# SCH_Beginner_project_2021-07-14.net
KiCad netlist of a schematic drawn in EasyEDA
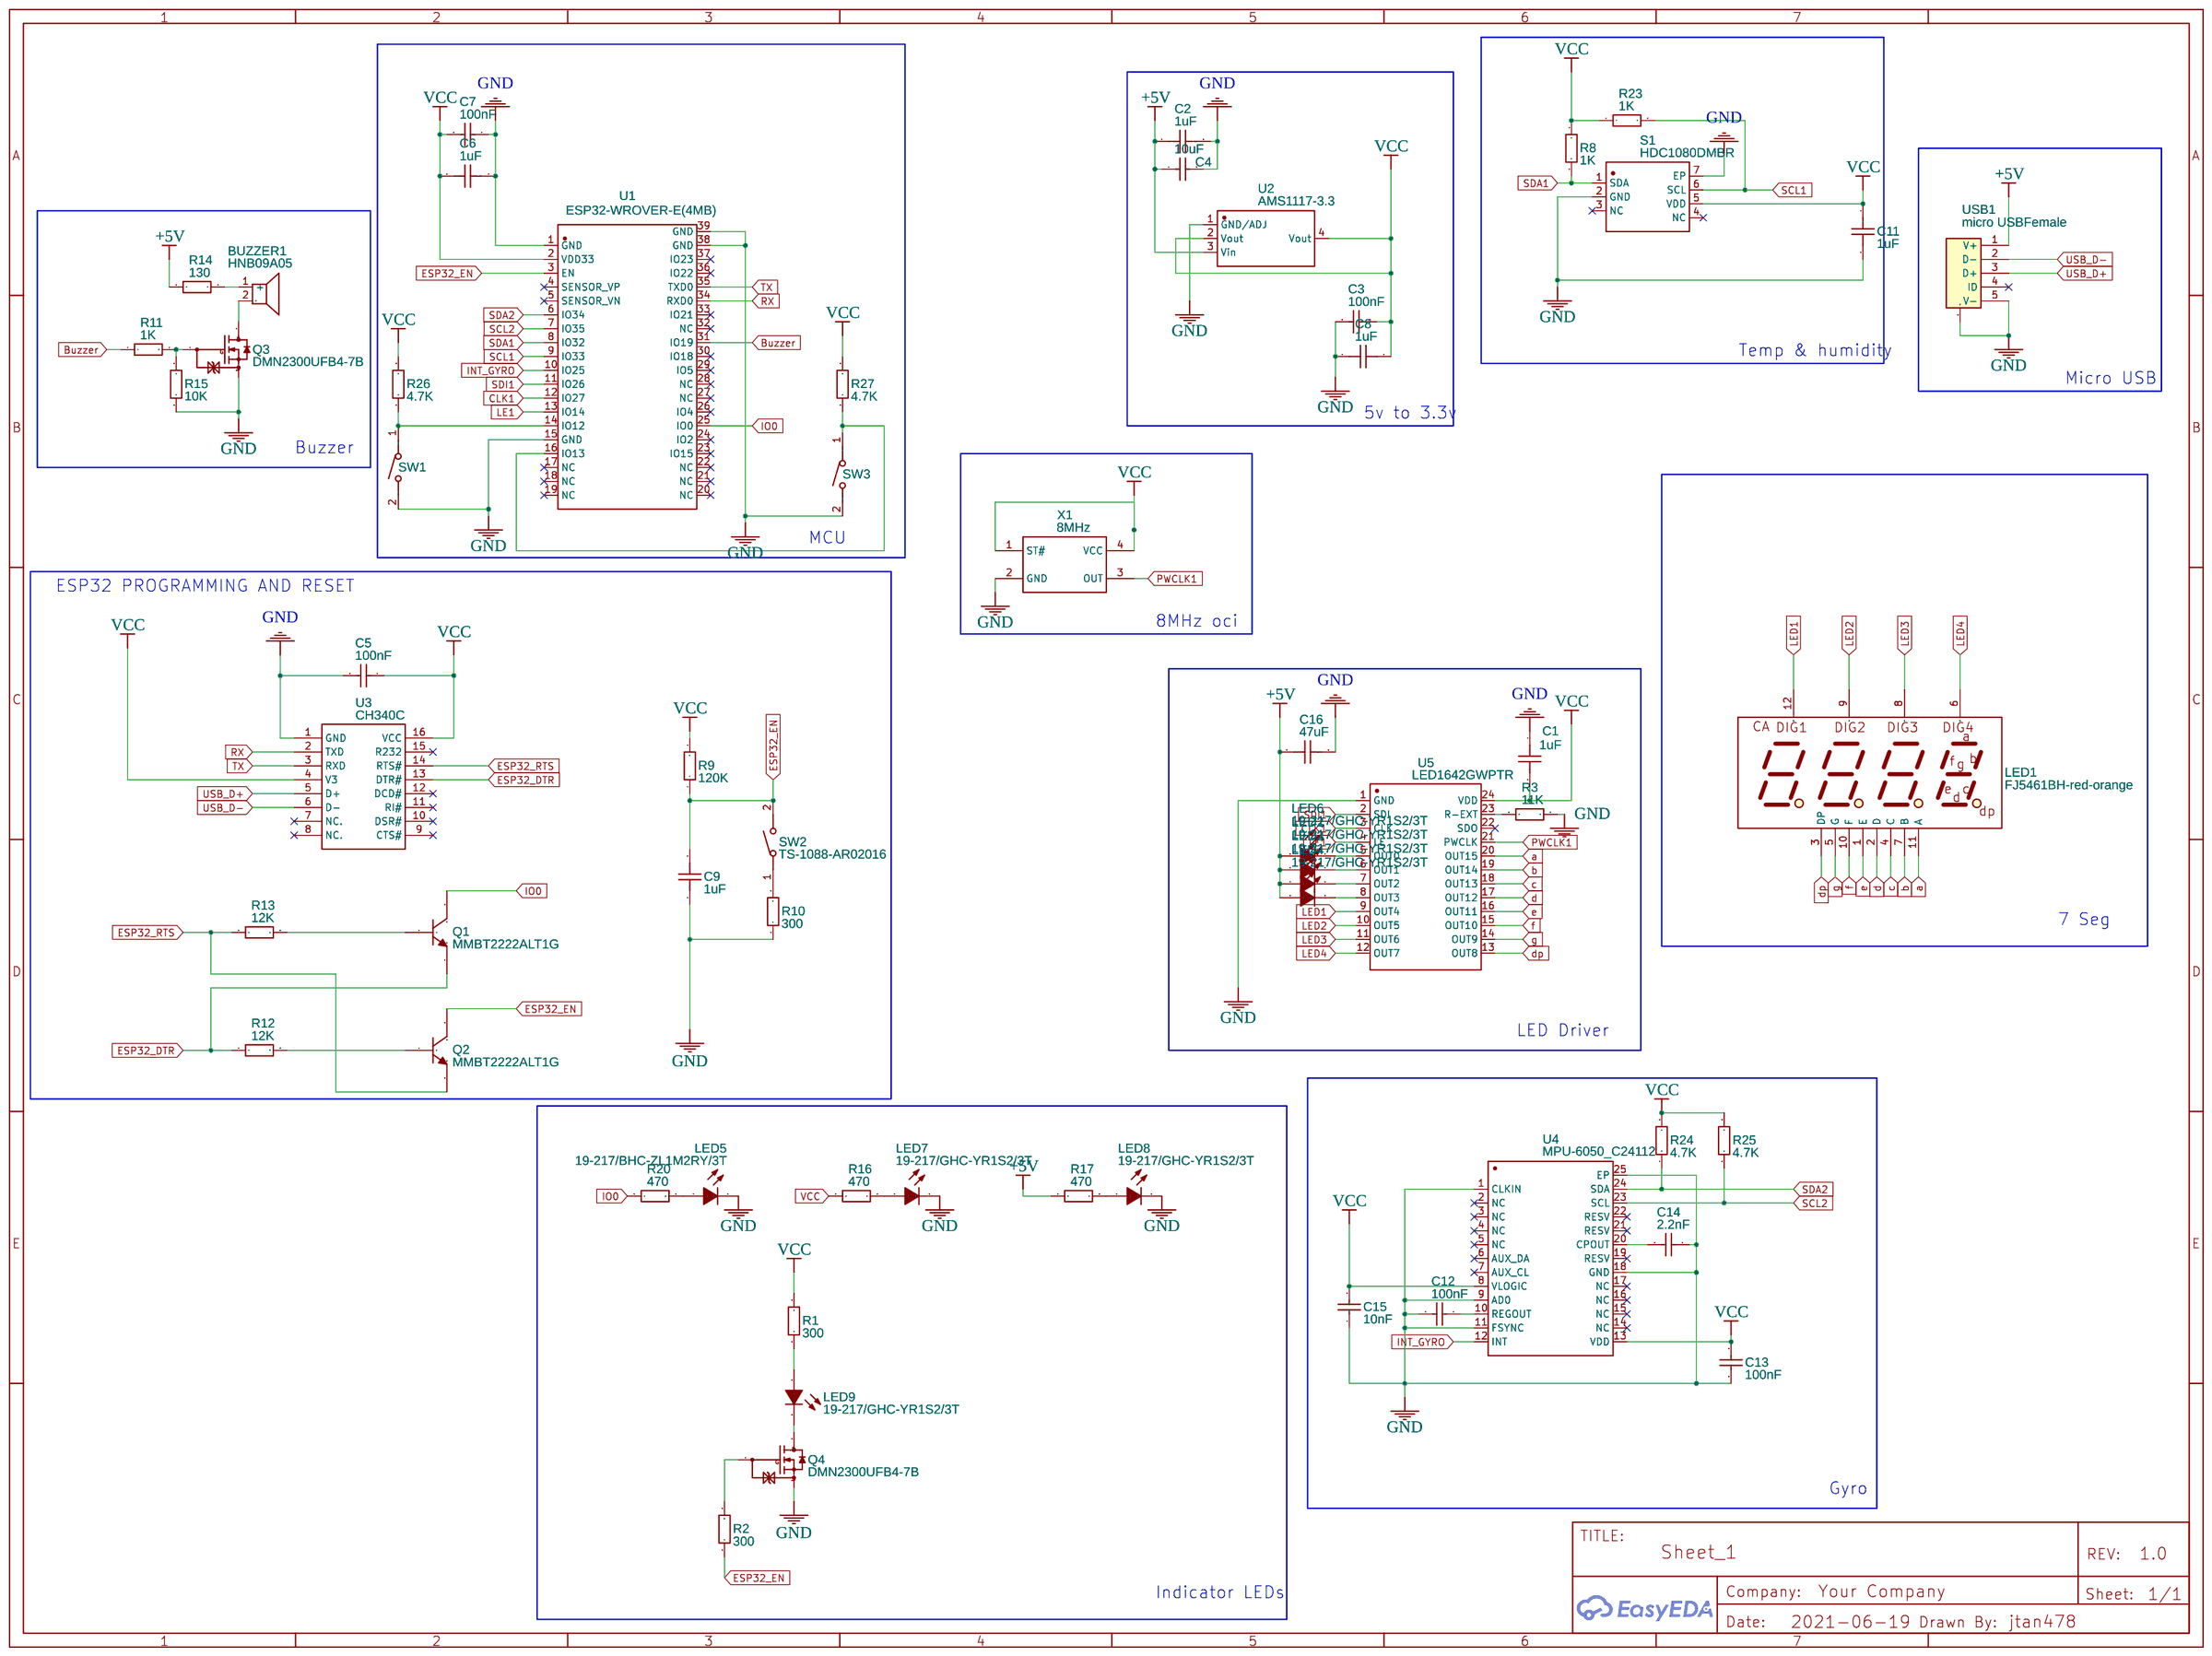
[diagram p0: schematic sheet]

(export (version "E")
  (design (tool "Eeschema 10.0.6"))
  (components
    (comp (ref "BUZZER1")
      (value "HNB09A05")
      (fields (field (name "BOM_Supplier Part") "C96493"))
      (libsource (lib "") (part "HNB09A05"))
    )
    (comp (ref "C1")
      (value "1uF")
      (fields
        (field (name "BOM_Manufacturer Part") "CL05A105KA5NQNC")
        (field (name "BOM_Supplier Part") "C52923")
      )
      (libsource (lib "") (part "CL05A105KA5NQNC_1"))
    )
    (comp (ref "C2")
      (value "1uF")
      (fields
        (field (name "BOM_Manufacturer Part") "CL05A105KA5NQNC")
        (field (name "BOM_Supplier Part") "C52923")
      )
      (libsource (lib "") (part "CL05A105KA5NQNC_3"))
    )
    (comp (ref "C3")
      (value "100nF")
      (fields
        (field (name "BOM_Manufacturer Part") "CL05B104KO5NNNC")
        (field (name "BOM_Supplier Part") "C1525")
      )
      (libsource (lib "") (part "CL05B104KO5NNNC"))
    )
    (comp (ref "C4")
      (value "10uF")
      (fields
        (field (name "BOM_Manufacturer Part") "CL05A106MQ5NUNC")
        (field (name "BOM_Supplier Part") "C15525")
      )
      (libsource (lib "") (part "CL05A106MQ5NUNC"))
    )
    (comp (ref "C5")
      (value "100nF")
      (fields
        (field (name "BOM_Manufacturer Part") "CL05B104KO5NNNC")
        (field (name "BOM_Supplier Part") "C1525")
      )
      (libsource (lib "") (part "CL05B104KO5NNNC"))
    )
    (comp (ref "C6")
      (value "1uF")
      (fields
        (field (name "BOM_Manufacturer Part") "CL05A105KA5NQNC")
        (field (name "BOM_Supplier Part") "C52923")
      )
      (libsource (lib "") (part "CL05A105KA5NQNC_2"))
    )
    (comp (ref "C7")
      (value "100nF")
      (fields
        (field (name "BOM_Manufacturer Part") "CL05B104KO5NNNC")
        (field (name "BOM_Supplier Part") "C1525")
      )
      (libsource (lib "") (part "CL05B104KO5NNNC"))
    )
    (comp (ref "C8")
      (value "1uF")
      (fields
        (field (name "BOM_Manufacturer Part") "CL05A105KA5NQNC")
        (field (name "BOM_Supplier Part") "C52923")
      )
      (libsource (lib "") (part "CL05A105KA5NQNC_3"))
    )
    (comp (ref "C9")
      (value "1uF")
      (fields
        (field (name "BOM_Manufacturer Part") "CL05A105KA5NQNC")
        (field (name "BOM_Supplier Part") "C52923")
      )
      (libsource (lib "") (part "CL05A105KA5NQNC"))
    )
    (comp (ref "C11")
      (value "1uF")
      (fields
        (field (name "BOM_Manufacturer Part") "CL05A105KA5NQNC")
        (field (name "BOM_Supplier Part") "C52923")
      )
      (libsource (lib "") (part "CL05A105KA5NQNC_1"))
    )
    (comp (ref "C12")
      (value "100nF")
      (fields
        (field (name "BOM_Manufacturer Part") "CL05B104KO5NNNC")
        (field (name "BOM_Supplier Part") "C1525")
      )
      (libsource (lib "") (part "CL05B104KO5NNNC"))
    )
    (comp (ref "C13")
      (value "100nF")
      (fields
        (field (name "BOM_Manufacturer Part") "CL05B104KO5NNNC")
        (field (name "BOM_Supplier Part") "C1525")
      )
      (libsource (lib "") (part "CL05B104KO5NNNC_1"))
    )
    (comp (ref "C14")
      (value "2.2nF")
      (fields
        (field (name "BOM_Manufacturer Part") "0402B222K500NT")
        (field (name "BOM_Supplier Part") "C1531")
      )
      (libsource (lib "") (part "0402B222K500NT"))
    )
    (comp (ref "C15")
      (value "10nF")
      (fields
        (field (name "BOM_Manufacturer Part") "CL05B103KB5NNNC")
        (field (name "BOM_Supplier Part") "C15195")
      )
      (libsource (lib "") (part "CL05B103KB5NNNC"))
    )
    (comp (ref "C16")
      (value "47uF")
      (fields
        (field (name "BOM_Manufacturer Part") "CL31A476MPHNNNE")
        (field (name "BOM_Supplier Part") "C96123")
      )
      (libsource (lib "") (part "CL31A476MPHNNNE"))
    )
    (comp (ref "LED1")
      (value "FJ5461BH-red-orange")
      (fields
        (field (name "BOM_Manufacturer Part") "FJ5461BH 橙红")
        (field (name "BOM_Supplier Part") "C10713")
      )
      (libsource (lib "") (part "FJ5461BH-red-orange"))
    )
    (comp (ref "LED2")
      (value "19-217/GHC-YR1S2/3T")
      (fields (field (name "BOM_Supplier Part") "C72043"))
      (libsource (lib "") (part "19-217/GHC-YR1S2/3T"))
    )
    (comp (ref "LED3")
      (value "19-217/GHC-YR1S2/3T")
      (fields (field (name "BOM_Supplier Part") "C72043"))
      (libsource (lib "") (part "19-217/GHC-YR1S2/3T"))
    )
    (comp (ref "LED4")
      (value "19-217/GHC-YR1S2/3T")
      (fields (field (name "BOM_Supplier Part") "C72043"))
      (libsource (lib "") (part "19-217/GHC-YR1S2/3T"))
    )
    (comp (ref "LED5")
      (value "19-217/BHC-ZL1M2RY/3T")
      (fields (field (name "BOM_Supplier Part") "C72041"))
      (libsource (lib "") (part "19-217/BHC-ZL1M2RY/3T"))
    )
    (comp (ref "LED6")
      (value "19-217/GHC-YR1S2/3T")
      (fields (field (name "BOM_Supplier Part") "C72043"))
      (libsource (lib "") (part "19-217/GHC-YR1S2/3T"))
    )
    (comp (ref "LED7")
      (value "19-217/GHC-YR1S2/3T")
      (fields (field (name "BOM_Supplier Part") "C72043"))
      (libsource (lib "") (part "19-217/GHC-YR1S2/3T"))
    )
    (comp (ref "LED8")
      (value "19-217/GHC-YR1S2/3T")
      (fields (field (name "BOM_Supplier Part") "C72043"))
      (libsource (lib "") (part "19-217/GHC-YR1S2/3T"))
    )
    (comp (ref "LED9")
      (value "19-217/GHC-YR1S2/3T")
      (fields (field (name "BOM_Supplier Part") "C72043"))
      (libsource (lib "") (part "19-217/GHC-YR1S2/3T_1"))
    )
    (comp (ref "Q1")
      (value "MMBT2222ALT1G")
      (fields (field (name "BOM_Supplier Part") "C82460"))
      (libsource (lib "") (part "MMBT2222ALT1G"))
    )
    (comp (ref "Q2")
      (value "MMBT2222ALT1G")
      (fields (field (name "BOM_Supplier Part") "C82460"))
      (libsource (lib "") (part "MMBT2222ALT1G"))
    )
    (comp (ref "Q3")
      (value "DMN2300UFB4-7B")
      (fields (field (name "BOM_Supplier Part") "C154728"))
      (libsource (lib "") (part "DMN2300UFB4-7B"))
    )
    (comp (ref "Q4")
      (value "DMN2300UFB4-7B")
      (fields (field (name "BOM_Supplier Part") "C154728"))
      (libsource (lib "") (part "DMN2300UFB4-7B"))
    )
    (comp (ref "R1")
      (value "300")
      (fields
        (field (name "BOM_Manufacturer Part") "0402WGF3000TCE")
        (field (name "BOM_Supplier Part") "C25102")
      )
      (libsource (lib "") (part "0402WGF3000TCE"))
    )
    (comp (ref "R2")
      (value "300")
      (fields
        (field (name "BOM_Manufacturer Part") "0402WGF3000TCE")
        (field (name "BOM_Supplier Part") "C25102")
      )
      (libsource (lib "") (part "0402WGF3000TCE"))
    )
    (comp (ref "R3")
      (value "11K")
      (fields
        (field (name "BOM_Manufacturer Part") "0603WAF1102T5E")
        (field (name "BOM_Supplier Part") "C25950")
      )
      (libsource (lib "") (part "0603WAF1102T5E"))
    )
    (comp (ref "R8")
      (value "1K")
      (fields
        (field (name "BOM_Manufacturer Part") "0603WAF1001T5E")
        (field (name "BOM_Supplier Part") "C21190")
      )
      (libsource (lib "") (part "0603WAF1001T5E_1"))
    )
    (comp (ref "R9")
      (value "120K")
      (fields
        (field (name "BOM_Manufacturer Part") "0402WGF1203TCE")
        (field (name "BOM_Supplier Part") "C25750")
      )
      (libsource (lib "") (part "0402WGF1203TCE"))
    )
    (comp (ref "R10")
      (value "300")
      (fields
        (field (name "BOM_Manufacturer Part") "0402WGF3000TCE")
        (field (name "BOM_Supplier Part") "C25102")
      )
      (libsource (lib "") (part "0402WGF3000TCE"))
    )
    (comp (ref "R11")
      (value "1K")
      (fields
        (field (name "BOM_Manufacturer Part") "0603WAF1001T5E")
        (field (name "BOM_Supplier Part") "C21190")
      )
      (libsource (lib "") (part "0603WAF1001T5E"))
    )
    (comp (ref "R12")
      (value "12K")
      (fields
        (field (name "BOM_Manufacturer Part") "0402WGF1202TCE")
        (field (name "BOM_Supplier Part") "C25752")
      )
      (libsource (lib "") (part "0402WGF1202TCE"))
    )
    (comp (ref "R13")
      (value "12K")
      (fields
        (field (name "BOM_Manufacturer Part") "0402WGF1202TCE")
        (field (name "BOM_Supplier Part") "C25752")
      )
      (libsource (lib "") (part "0402WGF1202TCE"))
    )
    (comp (ref "R14")
      (value "130")
      (fields
        (field (name "BOM_Manufacturer Part") "0603WAF1300T5E")
        (field (name "BOM_Supplier Part") "C22796")
      )
      (libsource (lib "") (part "0603WAF1300T5E"))
    )
    (comp (ref "R15")
      (value "10K")
      (fields
        (field (name "BOM_Manufacturer Part") "0603WAF1002T5E")
        (field (name "BOM_Supplier Part") "C25804")
      )
      (libsource (lib "") (part "0603WAF1002T5E"))
    )
    (comp (ref "R16")
      (value "470")
      (fields
        (field (name "BOM_Manufacturer Part") "0402WGF4700TCE")
        (field (name "BOM_Supplier Part") "C25117")
      )
      (libsource (lib "") (part "0402WGF4700TCE"))
    )
    (comp (ref "R17")
      (value "470")
      (fields
        (field (name "BOM_Manufacturer Part") "0402WGF4700TCE")
        (field (name "BOM_Supplier Part") "C25117")
      )
      (libsource (lib "") (part "0402WGF4700TCE"))
    )
    (comp (ref "R20")
      (value "470")
      (fields
        (field (name "BOM_Manufacturer Part") "0402WGF4700TCE")
        (field (name "BOM_Supplier Part") "C25117")
      )
      (libsource (lib "") (part "0402WGF4700TCE"))
    )
    (comp (ref "R23")
      (value "1K")
      (fields
        (field (name "BOM_Manufacturer Part") "0603WAF1001T5E")
        (field (name "BOM_Supplier Part") "C21190")
      )
      (libsource (lib "") (part "0603WAF1001T5E"))
    )
    (comp (ref "R24")
      (value "4.7K")
      (fields
        (field (name "BOM_Manufacturer Part") "0402WGF4701TCE")
        (field (name "BOM_Supplier Part") "C25900")
      )
      (libsource (lib "") (part "0402WGF4701TCE"))
    )
    (comp (ref "R25")
      (value "4.7K")
      (fields
        (field (name "BOM_Manufacturer Part") "0402WGF4701TCE")
        (field (name "BOM_Supplier Part") "C25900")
      )
      (libsource (lib "") (part "0402WGF4701TCE"))
    )
    (comp (ref "R26")
      (value "4.7K")
      (fields
        (field (name "BOM_Manufacturer Part") "0402WGF4701TCE")
        (field (name "BOM_Supplier Part") "C25900")
      )
      (libsource (lib "") (part "0402WGF4701TCE"))
    )
    (comp (ref "R27")
      (value "4.7K")
      (fields
        (field (name "BOM_Manufacturer Part") "0402WGF4701TCE")
        (field (name "BOM_Supplier Part") "C25900")
      )
      (libsource (lib "") (part "0402WGF4701TCE"))
    )
    (comp (ref "S1")
      (value "HDC1080DMBR")
      (fields (field (name "BOM_Supplier Part") "C82227"))
      (libsource (lib "") (part "HDC1080DMBR"))
    )
    (comp (ref "SW1")
      (value "TS-1088-AR02016")
      (fields (field (name "BOM_Supplier Part") "C720477"))
      (libsource (lib "") (part "TS-1088-AR02016"))
    )
    (comp (ref "SW2")
      (value "TS-1088-AR02016")
      (fields (field (name "BOM_Supplier Part") "C720477"))
      (libsource (lib "") (part "TS-1088-AR02016_1"))
    )
    (comp (ref "SW3")
      (value "TS-1088-AR02016")
      (fields (field (name "BOM_Supplier Part") "C720477"))
      (libsource (lib "") (part "TS-1088-AR02016"))
    )
    (comp (ref "U1")
      (value "ESP32-WROVER-E(4MB)")
      (fields (field (name "BOM_Supplier Part") "C529587"))
      (libsource (lib "") (part "ESP32-WROVER-E(4MB)"))
    )
    (comp (ref "U2")
      (value "AMS1117-3.3")
      (fields (field (name "BOM_Supplier Part") "C6186"))
      (libsource (lib "") (part "AMS1117-3.3"))
    )
    (comp (ref "U3")
      (value "CH340C")
      (fields (field (name "BOM_Supplier Part") "C84681"))
      (libsource (lib "") (part "CH340C"))
    )
    (comp (ref "U4")
      (value "MPU-6050_C24112")
      (fields (field (name "BOM_Manufacturer Part") "MPU-6050") (field (name "BOM_Supplier Part") "C24112"))
      (libsource (lib "") (part "MPU-6050_C24112"))
    )
    (comp (ref "U5")
      (value "LED1642GWPTR")
      (fields (field (name "BOM_Supplier Part") "C131193"))
      (libsource (lib "") (part "LED1642GWPTR"))
    )
    (comp (ref "USB1")
      (value "micro USBFemale")
      (fields (field (name "BOM_Supplier Part") "C10418"))
      (libsource (lib "") (part "micro USBFemale"))
    )
    (comp (ref "X1")
      (value "8MHz")
      (fields
        (field (name "BOM_Manufacturer Part") "Q33310F70055100")
        (field (name "BOM_Supplier Part") "C70556")
      )
      (libsource (lib "") (part "Q33310F70055100"))
    )
  )
  (nets
    (net (code "1") (name "+5V") (class "Default")
      (node (ref "C16") (pin "1") (pinfunction "1_1") (pintype "unspecified"))
      (node (ref "C2") (pin "1") (pinfunction "1_1") (pintype "unspecified"))
      (node (ref "C4") (pin "1") (pinfunction "1_1") (pintype "input"))
      (node (ref "LED2") (pin "1") (pinfunction "A_1") (pintype "input"))
      (node (ref "LED3") (pin "1") (pinfunction "A_1") (pintype "input"))
      (node (ref "LED4") (pin "1") (pinfunction "A_1") (pintype "input"))
      (node (ref "LED6") (pin "1") (pinfunction "A_1") (pintype "input"))
      (node (ref "R14") (pin "1") (pinfunction "1_1") (pintype "input"))
      (node (ref "R17") (pin "1") (pinfunction "1_1") (pintype "input"))
      (node (ref "U2") (pin "3") (pinfunction "Vin_3") (pintype "unspecified"))
      (node (ref "USB1") (pin "1") (pinfunction "V+_1") (pintype "unspecified"))
    )
    (net (code "2") (name "Buzzer") (class "Default")
      (node (ref "R11") (pin "1") (pinfunction "1_1") (pintype "input"))
      (node (ref "U1") (pin "31") (pinfunction "IO19_31") (pintype "unspecified"))
    )
    (net (code "3") (name "CLK1") (class "Default")
      (node (ref "U1") (pin "12") (pinfunction "IO27_12") (pintype "unspecified"))
      (node (ref "U5") (pin "3") (pinfunction "CLK_3") (pintype "unspecified"))
    )
    (net (code "4") (name "ESP32_DTR") (class "Default")
      (node (ref "Q1") (pin "2") (pinfunction "E_2") (pintype "unspecified"))
      (node (ref "R12") (pin "1") (pinfunction "1_1") (pintype "input"))
      (node (ref "U3") (pin "13") (pinfunction "DTR#_13") (pintype "unspecified"))
    )
    (net (code "5") (name "ESP32_EN") (class "Default")
      (node (ref "C9") (pin "2") (pinfunction "2_2") (pintype "unspecified"))
      (node (ref "Q2") (pin "3") (pinfunction "C_3") (pintype "unspecified"))
      (node (ref "R2") (pin "1") (pinfunction "1_1") (pintype "input"))
      (node (ref "R9") (pin "1") (pinfunction "1_1") (pintype "input"))
      (node (ref "SW2") (pin "2") (pinfunction "2_2") (pintype "unspecified"))
      (node (ref "U1") (pin "3") (pinfunction "EN_3") (pintype "unspecified"))
    )
    (net (code "6") (name "ESP32_RTS") (class "Default")
      (node (ref "Q2") (pin "2") (pinfunction "E_2") (pintype "unspecified"))
      (node (ref "R13") (pin "1") (pinfunction "1_1") (pintype "input"))
      (node (ref "U3") (pin "14") (pinfunction "RTS#_14") (pintype "unspecified"))
    )
    (net (code "7") (name "GND") (class "Default")
      (node (ref "C1") (pin "1") (pinfunction "1_1") (pintype "unspecified"))
      (node (ref "C11") (pin "2") (pinfunction "2_2") (pintype "unspecified"))
      (node (ref "C12") (pin "2") (pinfunction "2_2") (pintype "input"))
      (node (ref "C13") (pin "2") (pinfunction "2_2") (pintype "input"))
      (node (ref "C14") (pin "1") (pinfunction "1_1") (pintype "input"))
      (node (ref "C15") (pin "1") (pinfunction "1_1") (pintype "input"))
      (node (ref "C16") (pin "2") (pinfunction "2_2") (pintype "unspecified"))
      (node (ref "C2") (pin "2") (pinfunction "2_2") (pintype "unspecified"))
      (node (ref "C3") (pin "2") (pinfunction "2_2") (pintype "input"))
      (node (ref "C4") (pin "2") (pinfunction "2_2") (pintype "input"))
      (node (ref "C5") (pin "2") (pinfunction "2_2") (pintype "input"))
      (node (ref "C6") (pin "1") (pinfunction "1_1") (pintype "unspecified"))
      (node (ref "C7") (pin "1") (pinfunction "1_1") (pintype "input"))
      (node (ref "C8") (pin "1") (pinfunction "1_1") (pintype "unspecified"))
      (node (ref "C9") (pin "1") (pinfunction "1_1") (pintype "unspecified"))
      (node (ref "LED5") (pin "2") (pinfunction "C_2") (pintype "input"))
      (node (ref "LED7") (pin "2") (pinfunction "C_2") (pintype "input"))
      (node (ref "LED8") (pin "2") (pinfunction "C_2") (pintype "input"))
      (node (ref "Q3") (pin "3") (pinfunction "S_3") (pintype "unspecified"))
      (node (ref "Q4") (pin "3") (pinfunction "S_3") (pintype "unspecified"))
      (node (ref "R10") (pin "1") (pinfunction "1_1") (pintype "input"))
      (node (ref "R15") (pin "2") (pinfunction "2_2") (pintype "input"))
      (node (ref "R3") (pin "2") (pinfunction "2_2") (pintype "input"))
      (node (ref "S1") (pin "2") (pinfunction "GND_2") (pintype "unspecified"))
      (node (ref "S1") (pin "7") (pinfunction "EP_7") (pintype "unspecified"))
      (node (ref "SW1") (pin "2") (pinfunction "2_2") (pintype "unspecified"))
      (node (ref "SW3") (pin "2") (pinfunction "2_2") (pintype "unspecified"))
      (node (ref "U1") (pin "1") (pinfunction "GND_1") (pintype "unspecified"))
      (node (ref "U1") (pin "15") (pinfunction "GND_15") (pintype "unspecified"))
      (node (ref "U1") (pin "38") (pinfunction "GND_38") (pintype "unspecified"))
      (node (ref "U1") (pin "39") (pinfunction "GND_39") (pintype "unspecified"))
      (node (ref "U2") (pin "1") (pinfunction "GND/ADJ_1") (pintype "unspecified"))
      (node (ref "U3") (pin "1") (pinfunction "GND_1") (pintype "unspecified"))
      (node (ref "U4") (pin "1") (pinfunction "CLKIN_1") (pintype "unspecified"))
      (node (ref "U4") (pin "11") (pinfunction "FSYNC_11") (pintype "unspecified"))
      (node (ref "U4") (pin "18") (pinfunction "GND_18") (pintype "unspecified"))
      (node (ref "U4") (pin "25") (pinfunction "EP_25") (pintype "unspecified"))
      (node (ref "U4") (pin "9") (pinfunction "AD0_9") (pintype "unspecified"))
      (node (ref "U5") (pin "1") (pinfunction "GND_1") (pintype "unspecified"))
      (node (ref "USB1") (pin "0") (pinfunction "MTN_0") (pintype "input"))
      (node (ref "USB1") (pin "5") (pinfunction "V-_5") (pintype "unspecified"))
      (node (ref "X1") (pin "2") (pinfunction "GND_2") (pintype "unspecified"))
    )
    (net (code "8") (name "INT_GYRO") (class "Default")
      (node (ref "U1") (pin "10") (pinfunction "IO25_10") (pintype "unspecified"))
      (node (ref "U4") (pin "12") (pinfunction "INT_12") (pintype "unspecified"))
    )
    (net (code "9") (name "IO0") (class "Default")
      (node (ref "Q1") (pin "3") (pinfunction "C_3") (pintype "unspecified"))
      (node (ref "R20") (pin "1") (pinfunction "1_1") (pintype "input"))
      (node (ref "U1") (pin "25") (pinfunction "IO0_25") (pintype "unspecified"))
    )
    (net (code "10") (name "LE1") (class "Default")
      (node (ref "U1") (pin "13") (pinfunction "IO14_13") (pintype "unspecified"))
      (node (ref "U5") (pin "4") (pinfunction "LE_4") (pintype "unspecified"))
    )
    (net (code "11") (name "LED1") (class "Default")
      (node (ref "LED1") (pin "12") (pinfunction "DIG1_12") (pintype "input"))
      (node (ref "U5") (pin "9") (pinfunction "OUT4_9") (pintype "unspecified"))
    )
    (net (code "12") (name "LED2") (class "Default")
      (node (ref "LED1") (pin "9") (pinfunction "DIG2_9") (pintype "input"))
      (node (ref "U5") (pin "10") (pinfunction "OUT5_10") (pintype "unspecified"))
    )
    (net (code "13") (name "LED3") (class "Default")
      (node (ref "LED1") (pin "8") (pinfunction "DIG3_8") (pintype "input"))
      (node (ref "U5") (pin "11") (pinfunction "OUT6_11") (pintype "unspecified"))
    )
    (net (code "14") (name "LED4") (class "Default")
      (node (ref "LED1") (pin "6") (pinfunction "DIG4_6") (pintype "input"))
      (node (ref "U5") (pin "12") (pinfunction "OUT7_12") (pintype "unspecified"))
    )
    (net (code "15") (name "Net-(BUZZER1-+)") (class "Default")
      (node (ref "BUZZER1") (pin "1") (pinfunction "+_1") (pintype "unspecified"))
      (node (ref "R14") (pin "2") (pinfunction "2_2") (pintype "input"))
    )
    (net (code "16") (name "Net-(LED2-C)") (class "Default")
      (node (ref "LED2") (pin "2") (pinfunction "C_2") (pintype "input"))
      (node (ref "U5") (pin "6") (pinfunction "OUT1_6") (pintype "unspecified"))
    )
    (net (code "17") (name "Net-(LED3-C)") (class "Default")
      (node (ref "LED3") (pin "2") (pinfunction "C_2") (pintype "input"))
      (node (ref "U5") (pin "7") (pinfunction "OUT2_7") (pintype "unspecified"))
    )
    (net (code "18") (name "Net-(LED4-C)") (class "Default")
      (node (ref "LED4") (pin "2") (pinfunction "C_2") (pintype "input"))
      (node (ref "U5") (pin "8") (pinfunction "OUT3_8") (pintype "unspecified"))
    )
    (net (code "19") (name "Net-(LED5-A)") (class "Default")
      (node (ref "LED5") (pin "1") (pinfunction "A_1") (pintype "input"))
      (node (ref "R20") (pin "2") (pinfunction "2_2") (pintype "input"))
    )
    (net (code "20") (name "Net-(LED6-C)") (class "Default")
      (node (ref "LED6") (pin "2") (pinfunction "C_2") (pintype "input"))
      (node (ref "U5") (pin "5") (pinfunction "OUT0_5") (pintype "unspecified"))
    )
    (net (code "21") (name "Net-(LED7-A)") (class "Default")
      (node (ref "LED7") (pin "1") (pinfunction "A_1") (pintype "input"))
      (node (ref "R16") (pin "2") (pinfunction "2_2") (pintype "input"))
    )
    (net (code "22") (name "Net-(LED8-A)") (class "Default")
      (node (ref "LED8") (pin "1") (pinfunction "A_1") (pintype "input"))
      (node (ref "R17") (pin "2") (pinfunction "2_2") (pintype "input"))
    )
    (net (code "23") (name "Net-(LED9-A)") (class "Default")
      (node (ref "LED9") (pin "1") (pinfunction "A_1") (pintype "input"))
      (node (ref "R1") (pin "1") (pinfunction "1_1") (pintype "input"))
    )
    (net (code "24") (name "Net-(LED9-C)") (class "Default")
      (node (ref "LED9") (pin "2") (pinfunction "C_2") (pintype "input"))
      (node (ref "Q4") (pin "2") (pinfunction "D_2") (pintype "unspecified"))
    )
    (net (code "25") (name "Net-(Q1-B)") (class "Default")
      (node (ref "Q1") (pin "1") (pinfunction "B_1") (pintype "unspecified"))
      (node (ref "R13") (pin "2") (pinfunction "2_2") (pintype "input"))
    )
    (net (code "26") (name "Net-(Q2-B)") (class "Default")
      (node (ref "Q2") (pin "1") (pinfunction "B_1") (pintype "unspecified"))
      (node (ref "R12") (pin "2") (pinfunction "2_2") (pintype "input"))
    )
    (net (code "27") (name "Net-(Q3-D)") (class "Default")
      (node (ref "BUZZER1") (pin "2") (pinfunction "2_2") (pintype "unspecified"))
      (node (ref "Q3") (pin "2") (pinfunction "D_2") (pintype "unspecified"))
    )
    (net (code "28") (name "Net-(Q3-G)") (class "Default")
      (node (ref "Q3") (pin "1") (pinfunction "G_1") (pintype "unspecified"))
      (node (ref "R11") (pin "2") (pinfunction "2_2") (pintype "input"))
      (node (ref "R15") (pin "1") (pinfunction "1_1") (pintype "input"))
    )
    (net (code "29") (name "Net-(Q4-G)") (class "Default")
      (node (ref "Q4") (pin "1") (pinfunction "G_1") (pintype "unspecified"))
      (node (ref "R2") (pin "2") (pinfunction "2_2") (pintype "input"))
    )
    (net (code "30") (name "Net-(R10-Pad2)") (class "Default")
      (node (ref "R10") (pin "2") (pinfunction "2_2") (pintype "input"))
      (node (ref "SW2") (pin "1") (pinfunction "1_1") (pintype "unspecified"))
    )
    (net (code "31") (name "Net-(U1-IO12)") (class "Default")
      (node (ref "R26") (pin "1") (pinfunction "1_1") (pintype "input"))
      (node (ref "SW1") (pin "1") (pinfunction "1_1") (pintype "unspecified"))
      (node (ref "U1") (pin "14") (pinfunction "IO12_14") (pintype "unspecified"))
    )
    (net (code "32") (name "Net-(U1-IO13)") (class "Default")
      (node (ref "R27") (pin "1") (pinfunction "1_1") (pintype "input"))
      (node (ref "SW3") (pin "1") (pinfunction "1_1") (pintype "unspecified"))
      (node (ref "U1") (pin "16") (pinfunction "IO13_16") (pintype "unspecified"))
    )
    (net (code "33") (name "Net-(U4-CPOUT)") (class "Default")
      (node (ref "C14") (pin "2") (pinfunction "2_2") (pintype "input"))
      (node (ref "U4") (pin "20") (pinfunction "CPOUT_20") (pintype "unspecified"))
    )
    (net (code "34") (name "Net-(U4-REGOUT)") (class "Default")
      (node (ref "C12") (pin "1") (pinfunction "1_1") (pintype "input"))
      (node (ref "U4") (pin "10") (pinfunction "REGOUT_10") (pintype "unspecified"))
    )
    (net (code "35") (name "Net-(U5-R-EXT)") (class "Default")
      (node (ref "R3") (pin "1") (pinfunction "1_1") (pintype "input"))
      (node (ref "U5") (pin "23") (pinfunction "R-EXT_23") (pintype "unspecified"))
    )
    (net (code "36") (name "PWCLK1") (class "Default")
      (node (ref "U5") (pin "21") (pinfunction "PWCLK_21") (pintype "unspecified"))
      (node (ref "X1") (pin "3") (pinfunction "OUT_3") (pintype "unspecified"))
    )
    (net (code "37") (name "RX") (class "Default")
      (node (ref "U1") (pin "34") (pinfunction "RXD0_34") (pintype "unspecified"))
      (node (ref "U3") (pin "2") (pinfunction "TXD_2") (pintype "unspecified"))
    )
    (net (code "38") (name "SCL1") (class "Default")
      (node (ref "R23") (pin "2") (pinfunction "2_2") (pintype "input"))
      (node (ref "S1") (pin "6") (pinfunction "SCL_6") (pintype "unspecified"))
      (node (ref "U1") (pin "9") (pinfunction "IO33_9") (pintype "unspecified"))
    )
    (net (code "39") (name "SCL2") (class "Default")
      (node (ref "R25") (pin "1") (pinfunction "1_1") (pintype "input"))
      (node (ref "U1") (pin "7") (pinfunction "IO35_7") (pintype "unspecified"))
      (node (ref "U4") (pin "23") (pinfunction "SCL_23") (pintype "unspecified"))
    )
    (net (code "40") (name "SDA1") (class "Default")
      (node (ref "R8") (pin "2") (pinfunction "2_2") (pintype "input"))
      (node (ref "S1") (pin "1") (pinfunction "SDA_1") (pintype "unspecified"))
      (node (ref "U1") (pin "8") (pinfunction "IO32_8") (pintype "unspecified"))
    )
    (net (code "41") (name "SDA2") (class "Default")
      (node (ref "R24") (pin "1") (pinfunction "1_1") (pintype "input"))
      (node (ref "U1") (pin "6") (pinfunction "IO34_6") (pintype "unspecified"))
      (node (ref "U4") (pin "24") (pinfunction "SDA_24") (pintype "unspecified"))
    )
    (net (code "42") (name "SDI1") (class "Default")
      (node (ref "U1") (pin "11") (pinfunction "IO26_11") (pintype "unspecified"))
      (node (ref "U5") (pin "2") (pinfunction "SDI_2") (pintype "unspecified"))
    )
    (net (code "43") (name "TX") (class "Default")
      (node (ref "U1") (pin "35") (pinfunction "TXD0_35") (pintype "unspecified"))
      (node (ref "U3") (pin "3") (pinfunction "RXD_3") (pintype "unspecified"))
    )
    (net (code "44") (name "USB_D+") (class "Default")
      (node (ref "U3") (pin "5") (pinfunction "D+_5") (pintype "unspecified"))
      (node (ref "USB1") (pin "3") (pinfunction "D+_3") (pintype "unspecified"))
    )
    (net (code "45") (name "USB_D-") (class "Default")
      (node (ref "U3") (pin "6") (pinfunction "D-_6") (pintype "unspecified"))
      (node (ref "USB1") (pin "2") (pinfunction "D-_2") (pintype "unspecified"))
    )
    (net (code "46") (name "VCC") (class "Default")
      (node (ref "C1") (pin "2") (pinfunction "2_2") (pintype "unspecified"))
      (node (ref "C11") (pin "1") (pinfunction "1_1") (pintype "unspecified"))
      (node (ref "C13") (pin "1") (pinfunction "1_1") (pintype "input"))
      (node (ref "C15") (pin "2") (pinfunction "2_2") (pintype "input"))
      (node (ref "C3") (pin "1") (pinfunction "1_1") (pintype "input"))
      (node (ref "C5") (pin "1") (pinfunction "1_1") (pintype "input"))
      (node (ref "C6") (pin "2") (pinfunction "2_2") (pintype "unspecified"))
      (node (ref "C7") (pin "2") (pinfunction "2_2") (pintype "input"))
      (node (ref "C8") (pin "2") (pinfunction "2_2") (pintype "unspecified"))
      (node (ref "R1") (pin "2") (pinfunction "2_2") (pintype "input"))
      (node (ref "R16") (pin "1") (pinfunction "1_1") (pintype "input"))
      (node (ref "R23") (pin "1") (pinfunction "1_1") (pintype "input"))
      (node (ref "R24") (pin "2") (pinfunction "2_2") (pintype "input"))
      (node (ref "R25") (pin "2") (pinfunction "2_2") (pintype "input"))
      (node (ref "R26") (pin "2") (pinfunction "2_2") (pintype "input"))
      (node (ref "R27") (pin "2") (pinfunction "2_2") (pintype "input"))
      (node (ref "R8") (pin "1") (pinfunction "1_1") (pintype "input"))
      (node (ref "R9") (pin "2") (pinfunction "2_2") (pintype "input"))
      (node (ref "S1") (pin "5") (pinfunction "VDD_5") (pintype "unspecified"))
      (node (ref "U1") (pin "2") (pinfunction "VDD33_2") (pintype "unspecified"))
      (node (ref "U2") (pin "2") (pinfunction "Vout_2") (pintype "unspecified"))
      (node (ref "U2") (pin "4") (pinfunction "Vout_4") (pintype "unspecified"))
      (node (ref "U3") (pin "16") (pinfunction "VCC_16") (pintype "unspecified"))
      (node (ref "U3") (pin "4") (pinfunction "V3_4") (pintype "unspecified"))
      (node (ref "U4") (pin "13") (pinfunction "VDD_13") (pintype "unspecified"))
      (node (ref "U4") (pin "8") (pinfunction "VLOGIC_8") (pintype "unspecified"))
      (node (ref "U5") (pin "24") (pinfunction "VDD_24") (pintype "unspecified"))
      (node (ref "X1") (pin "1") (pinfunction "ST#_1") (pintype "unspecified"))
      (node (ref "X1") (pin "4") (pinfunction "VCC_4") (pintype "unspecified"))
    )
    (net (code "47") (name "a") (class "Default")
      (node (ref "LED1") (pin "11") (pinfunction "A_11") (pintype "input"))
      (node (ref "U5") (pin "20") (pinfunction "OUT15_20") (pintype "unspecified"))
    )
    (net (code "48") (name "b") (class "Default")
      (node (ref "LED1") (pin "7") (pinfunction "B_7") (pintype "input"))
      (node (ref "U5") (pin "19") (pinfunction "OUT14_19") (pintype "unspecified"))
    )
    (net (code "49") (name "c") (class "Default")
      (node (ref "LED1") (pin "4") (pinfunction "C_4") (pintype "input"))
      (node (ref "U5") (pin "18") (pinfunction "OUT13_18") (pintype "unspecified"))
    )
    (net (code "50") (name "d") (class "Default")
      (node (ref "LED1") (pin "2") (pinfunction "D_2") (pintype "input"))
      (node (ref "U5") (pin "17") (pinfunction "OUT12_17") (pintype "unspecified"))
    )
    (net (code "51") (name "dp") (class "Default")
      (node (ref "LED1") (pin "3") (pinfunction "DP_3") (pintype "input"))
      (node (ref "U5") (pin "13") (pinfunction "OUT8_13") (pintype "unspecified"))
    )
    (net (code "52") (name "e") (class "Default")
      (node (ref "LED1") (pin "1") (pinfunction "E_1") (pintype "input"))
      (node (ref "U5") (pin "16") (pinfunction "OUT11_16") (pintype "unspecified"))
    )
    (net (code "53") (name "f") (class "Default")
      (node (ref "LED1") (pin "10") (pinfunction "F_10") (pintype "input"))
      (node (ref "U5") (pin "15") (pinfunction "OUT10_15") (pintype "unspecified"))
    )
    (net (code "54") (name "g") (class "Default")
      (node (ref "LED1") (pin "5") (pinfunction "G_5") (pintype "input"))
      (node (ref "U5") (pin "14") (pinfunction "OUT9_14") (pintype "unspecified"))
    )
    (net (code "55") (name "unconnected-(S1-NC-Pad3)") (class "Default")
      (node (ref "S1") (pin "3") (pinfunction "NC_3") (pintype "unspecified+no_connect"))
    )
    (net (code "56") (name "unconnected-(S1-NC-Pad4)") (class "Default")
      (node (ref "S1") (pin "4") (pinfunction "NC_4") (pintype "unspecified+no_connect"))
    )
    (net (code "57") (name "unconnected-(U1-IO2-Pad24)") (class "Default")
      (node (ref "U1") (pin "24") (pinfunction "IO2_24") (pintype "unspecified+no_connect"))
    )
    (net (code "58") (name "unconnected-(U1-IO4-Pad26)") (class "Default")
      (node (ref "U1") (pin "26") (pinfunction "IO4_26") (pintype "unspecified+no_connect"))
    )
    (net (code "59") (name "unconnected-(U1-IO5-Pad29)") (class "Default")
      (node (ref "U1") (pin "29") (pinfunction "IO5_29") (pintype "unspecified+no_connect"))
    )
    (net (code "60") (name "unconnected-(U1-IO15-Pad23)") (class "Default")
      (node (ref "U1") (pin "23") (pinfunction "IO15_23") (pintype "unspecified+no_connect"))
    )
    (net (code "61") (name "unconnected-(U1-IO18-Pad30)") (class "Default")
      (node (ref "U1") (pin "30") (pinfunction "IO18_30") (pintype "unspecified+no_connect"))
    )
    (net (code "62") (name "unconnected-(U1-IO21-Pad33)") (class "Default")
      (node (ref "U1") (pin "33") (pinfunction "IO21_33") (pintype "unspecified+no_connect"))
    )
    (net (code "63") (name "unconnected-(U1-IO22-Pad36)") (class "Default")
      (node (ref "U1") (pin "36") (pinfunction "IO22_36") (pintype "unspecified+no_connect"))
    )
    (net (code "64") (name "unconnected-(U1-IO23-Pad37)") (class "Default")
      (node (ref "U1") (pin "37") (pinfunction "IO23_37") (pintype "unspecified+no_connect"))
    )
    (net (code "65") (name "unconnected-(U1-NC-Pad17)") (class "Default")
      (node (ref "U1") (pin "17") (pinfunction "NC_17") (pintype "unspecified+no_connect"))
    )
    (net (code "66") (name "unconnected-(U1-NC-Pad18)") (class "Default")
      (node (ref "U1") (pin "18") (pinfunction "NC_18") (pintype "unspecified+no_connect"))
    )
    (net (code "67") (name "unconnected-(U1-NC-Pad19)") (class "Default")
      (node (ref "U1") (pin "19") (pinfunction "NC_19") (pintype "unspecified+no_connect"))
    )
    (net (code "68") (name "unconnected-(U1-NC-Pad20)") (class "Default")
      (node (ref "U1") (pin "20") (pinfunction "NC_20") (pintype "unspecified+no_connect"))
    )
    (net (code "69") (name "unconnected-(U1-NC-Pad21)") (class "Default")
      (node (ref "U1") (pin "21") (pinfunction "NC_21") (pintype "unspecified+no_connect"))
    )
    (net (code "70") (name "unconnected-(U1-NC-Pad22)") (class "Default")
      (node (ref "U1") (pin "22") (pinfunction "NC_22") (pintype "unspecified+no_connect"))
    )
    (net (code "71") (name "unconnected-(U1-NC-Pad27)") (class "Default")
      (node (ref "U1") (pin "27") (pinfunction "NC_27") (pintype "unspecified+no_connect"))
    )
    (net (code "72") (name "unconnected-(U1-NC-Pad28)") (class "Default")
      (node (ref "U1") (pin "28") (pinfunction "NC_28") (pintype "unspecified+no_connect"))
    )
    (net (code "73") (name "unconnected-(U1-NC-Pad32)") (class "Default")
      (node (ref "U1") (pin "32") (pinfunction "NC_32") (pintype "unspecified+no_connect"))
    )
    (net (code "74") (name "unconnected-(U1-SENSOR_VN-Pad5)") (class "Default")
      (node (ref "U1") (pin "5") (pinfunction "SENSOR_VN_5") (pintype "unspecified+no_connect"))
    )
    (net (code "75") (name "unconnected-(U1-SENSOR_VP-Pad4)") (class "Default")
      (node (ref "U1") (pin "4") (pinfunction "SENSOR_VP_4") (pintype "unspecified+no_connect"))
    )
    (net (code "76") (name "unconnected-(U3-CTS#-Pad9)") (class "Default")
      (node (ref "U3") (pin "9") (pinfunction "CTS#_9") (pintype "unspecified+no_connect"))
    )
    (net (code "77") (name "unconnected-(U3-DCD#-Pad12)") (class "Default")
      (node (ref "U3") (pin "12") (pinfunction "DCD#_12") (pintype "unspecified+no_connect"))
    )
    (net (code "78") (name "unconnected-(U3-DSR#-Pad10)") (class "Default")
      (node (ref "U3") (pin "10") (pinfunction "DSR#_10") (pintype "unspecified+no_connect"))
    )
    (net (code "79") (name "unconnected-(U3-NC.-Pad7)") (class "Default")
      (node (ref "U3") (pin "7") (pinfunction "NC._7") (pintype "unspecified+no_connect"))
    )
    (net (code "80") (name "unconnected-(U3-NC.-Pad8)") (class "Default")
      (node (ref "U3") (pin "8") (pinfunction "NC._8") (pintype "unspecified+no_connect"))
    )
    (net (code "81") (name "unconnected-(U3-R232-Pad15)") (class "Default")
      (node (ref "U3") (pin "15") (pinfunction "R232_15") (pintype "unspecified+no_connect"))
    )
    (net (code "82") (name "unconnected-(U3-RI#-Pad11)") (class "Default")
      (node (ref "U3") (pin "11") (pinfunction "RI#_11") (pintype "unspecified+no_connect"))
    )
    (net (code "83") (name "unconnected-(U4-AUX_CL-Pad7)") (class "Default")
      (node (ref "U4") (pin "7") (pinfunction "AUX_CL_7") (pintype "unspecified+no_connect"))
    )
    (net (code "84") (name "unconnected-(U4-AUX_DA-Pad6)") (class "Default")
      (node (ref "U4") (pin "6") (pinfunction "AUX_DA_6") (pintype "unspecified+no_connect"))
    )
    (net (code "85") (name "unconnected-(U4-NC-Pad2)") (class "Default")
      (node (ref "U4") (pin "2") (pinfunction "NC_2") (pintype "unspecified+no_connect"))
    )
    (net (code "86") (name "unconnected-(U4-NC-Pad3)") (class "Default")
      (node (ref "U4") (pin "3") (pinfunction "NC_3") (pintype "unspecified+no_connect"))
    )
    (net (code "87") (name "unconnected-(U4-NC-Pad4)") (class "Default")
      (node (ref "U4") (pin "4") (pinfunction "NC_4") (pintype "unspecified+no_connect"))
    )
    (net (code "88") (name "unconnected-(U4-NC-Pad5)") (class "Default")
      (node (ref "U4") (pin "5") (pinfunction "NC_5") (pintype "unspecified+no_connect"))
    )
    (net (code "89") (name "unconnected-(U4-NC-Pad14)") (class "Default")
      (node (ref "U4") (pin "14") (pinfunction "NC_14") (pintype "unspecified+no_connect"))
    )
    (net (code "90") (name "unconnected-(U4-NC-Pad15)") (class "Default")
      (node (ref "U4") (pin "15") (pinfunction "NC_15") (pintype "unspecified+no_connect"))
    )
    (net (code "91") (name "unconnected-(U4-NC-Pad16)") (class "Default")
      (node (ref "U4") (pin "16") (pinfunction "NC_16") (pintype "unspecified+no_connect"))
    )
    (net (code "92") (name "unconnected-(U4-NC-Pad17)") (class "Default")
      (node (ref "U4") (pin "17") (pinfunction "NC_17") (pintype "unspecified+no_connect"))
    )
    (net (code "93") (name "unconnected-(U4-RESV-Pad19)") (class "Default")
      (node (ref "U4") (pin "19") (pinfunction "RESV_19") (pintype "unspecified+no_connect"))
    )
    (net (code "94") (name "unconnected-(U4-RESV-Pad21)") (class "Default")
      (node (ref "U4") (pin "21") (pinfunction "RESV_21") (pintype "unspecified+no_connect"))
    )
    (net (code "95") (name "unconnected-(U4-RESV-Pad22)") (class "Default")
      (node (ref "U4") (pin "22") (pinfunction "RESV_22") (pintype "unspecified+no_connect"))
    )
    (net (code "96") (name "unconnected-(U5-SDO-Pad22)") (class "Default")
      (node (ref "U5") (pin "22") (pinfunction "SDO_22") (pintype "unspecified+no_connect"))
    )
    (net (code "97") (name "unconnected-(USB1-ID-Pad4)") (class "Default")
      (node (ref "USB1") (pin "4") (pinfunction "ID_4") (pintype "unspecified+no_connect"))
    )
  )
)
